# Teensy_Intan_Module_JE_T36_v01_20180628.net
KiCad netlist of a schematic drawn in EAGLE
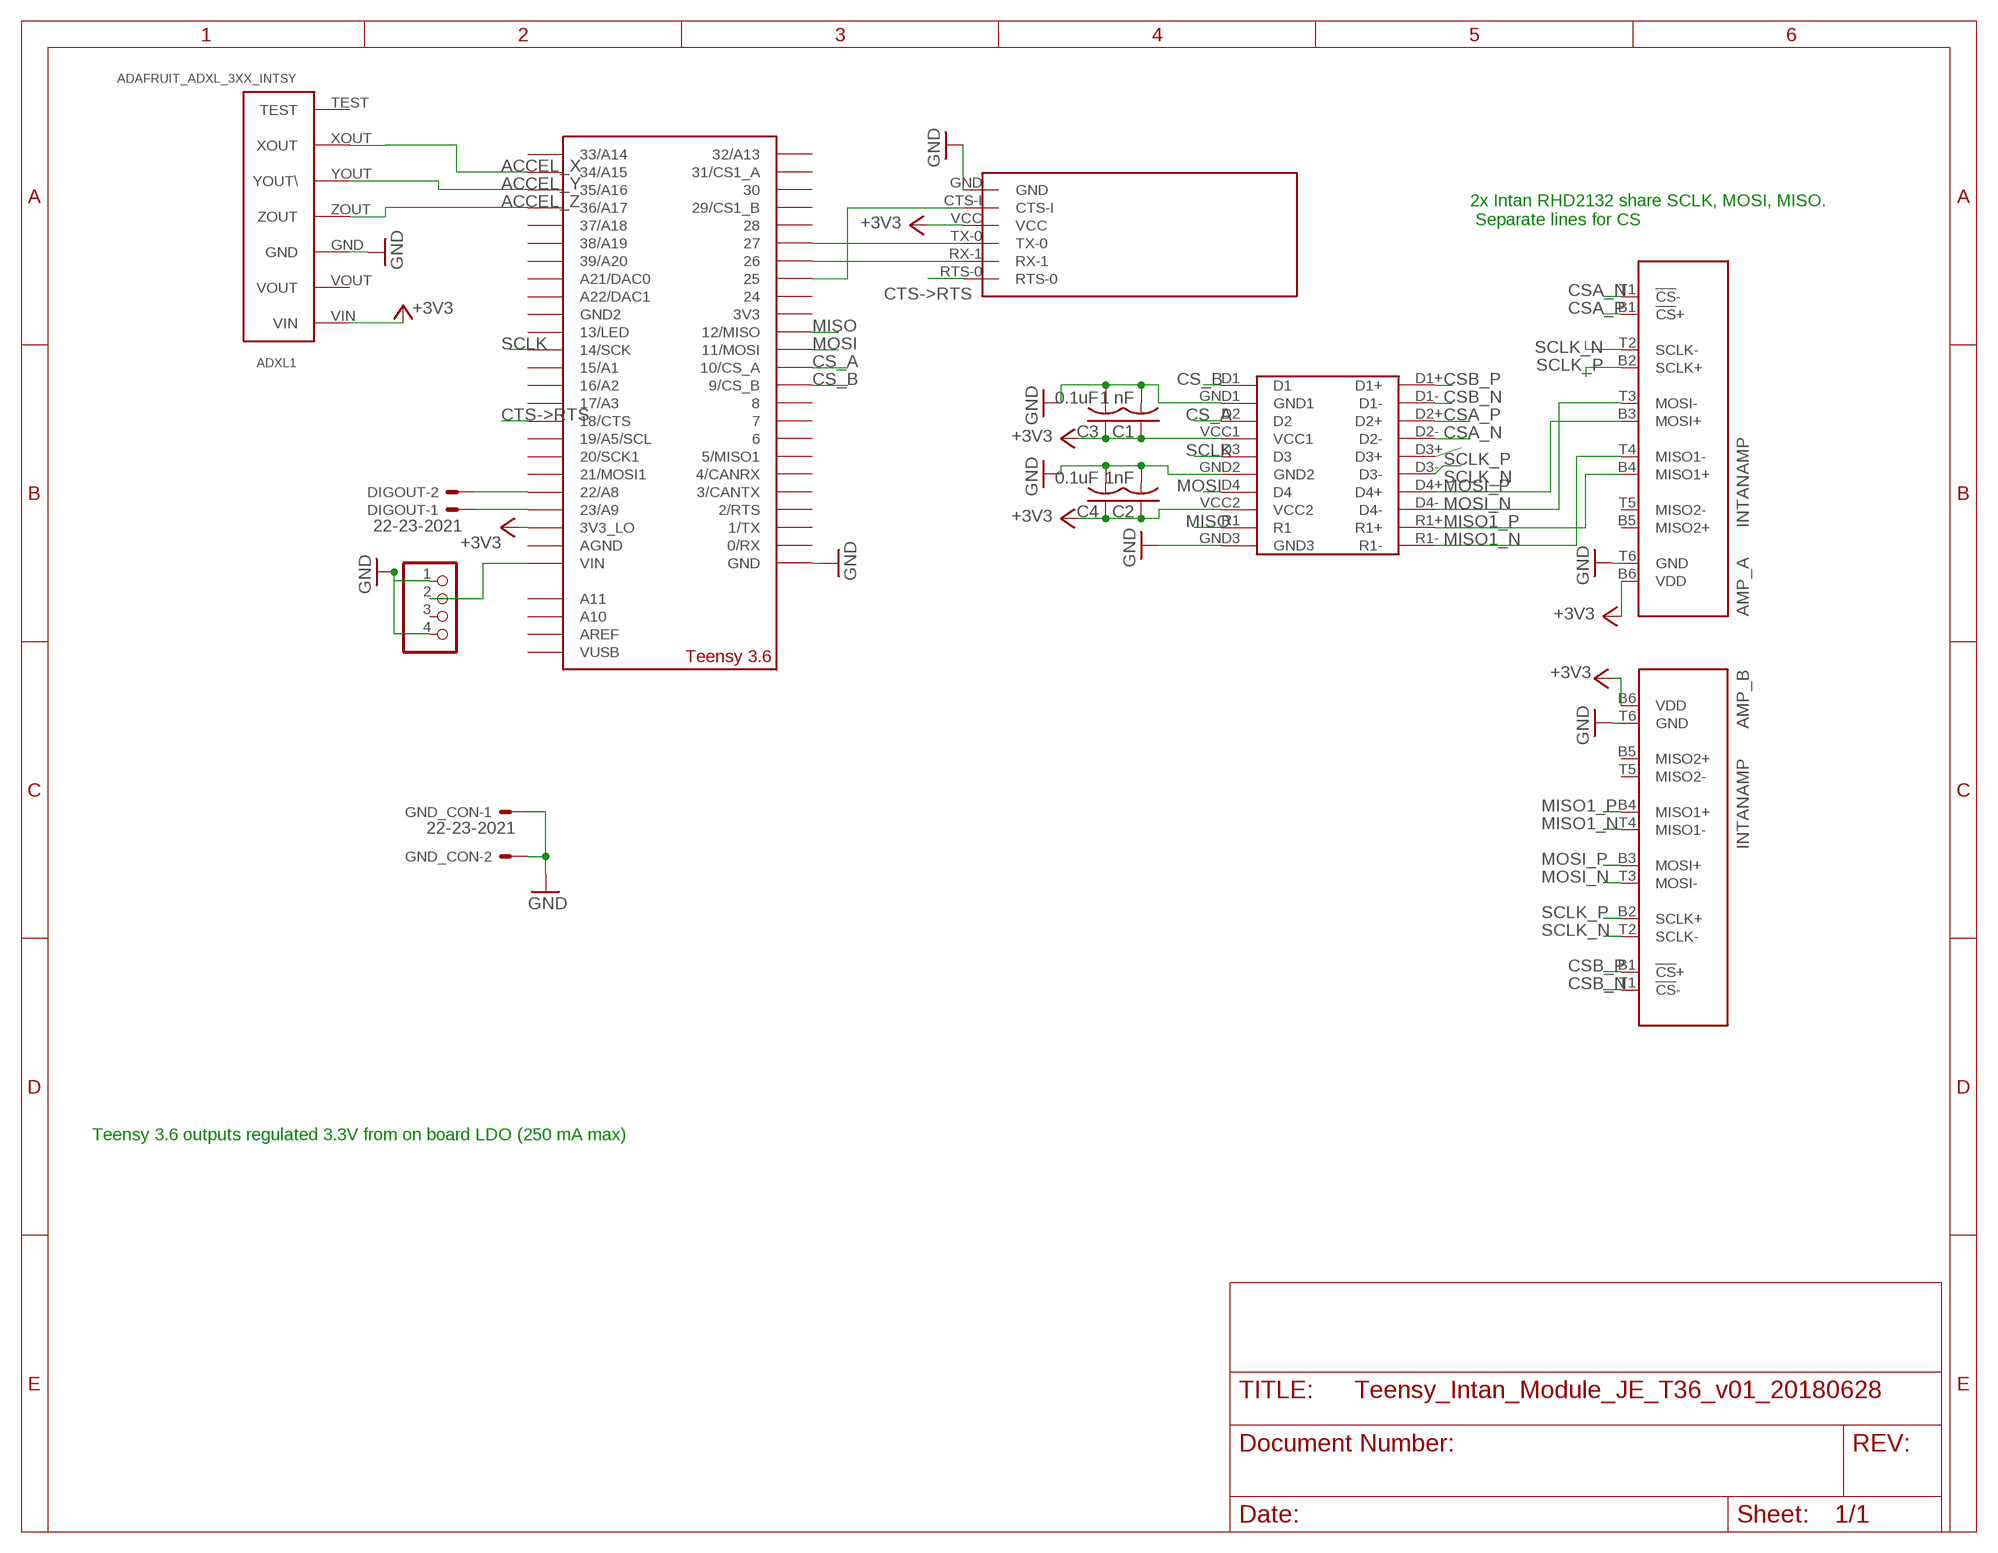
[diagram p0: schematic, sheet 1]

(export (version "E")
  (design (tool "Eeschema 10.0.6"))
  (components
    (comp (ref "ADXL1")
      (value "ADAFRUIT_ADXL_3XX_INTSY")
      (footprint "eagle-import:ADAFRUIT_ADXL_3XX")
      (libsource (lib "eagle-import") (part "ADAFRUIT_ADXL_3XX_INTSY"))
    )
    (comp (ref "AMP_A")
      (value "INTANAMP")
      (footprint "eagle-import:AMPBOARD")
      (libsource (lib "eagle-import") (part "INTANAMP"))
    )
    (comp (ref "AMP_B")
      (value "INTANAMP")
      (footprint "eagle-import:AMPBOARD")
      (libsource (lib "eagle-import") (part "INTANAMP"))
    )
    (comp (ref "C1")
      (value "1 nF")
      (footprint "eagle-import:C025-024X044")
      (libsource (lib "eagle-import") (part "C-US025-024X044"))
    )
    (comp (ref "C2")
      (value "1nF")
      (footprint "eagle-import:C025-024X044")
      (libsource (lib "eagle-import") (part "C-US025-024X044"))
    )
    (comp (ref "C3")
      (value "0.1uF")
      (footprint "eagle-import:C025-024X044")
      (libsource (lib "eagle-import") (part "C-US025-024X044"))
    )
    (comp (ref "C4")
      (value "0.1uF")
      (footprint "eagle-import:C025-024X044")
      (libsource (lib "eagle-import") (part "C-US025-024X044"))
    )
    (comp (ref "DIGOUT")
      (value "22-23-2021")
      (footprint "eagle-import:22-23-2021")
      (fields (field (name "MF") "MOLEX"))
      (libsource (lib "eagle-import") (part "22-23-2021"))
    )
    (comp (ref "GND_CON")
      (value "22-23-2021")
      (footprint "eagle-import:22-23-2021")
      (fields (field (name "MF") "MOLEX"))
      (libsource (lib "eagle-import") (part "22-23-2021"))
    )
    (comp (ref "RN42")
      (value "RN42")
      (footprint "eagle-import:RN42")
      (libsource (lib "eagle-import") (part "RN42"))
    )
    (comp (ref "SW1")
      (value "LiPoIn")
      (footprint "eagle-import:PADS-4")
      (libsource (lib "eagle-import") (part "PADS-4"))
    )
    (comp (ref "U$1")
      (value "SCHMARTBOARD20PIN")
      (footprint "eagle-import:SCHMARTBOARD20PIN")
      (libsource (lib "eagle-import") (part "SCHMARTBOARD20PIN"))
    )
    (comp (ref "U$2")
      (value "TEENSY_3.5/3.6_BASIC")
      (footprint "eagle-import:TEENSY_3.5_3.6_BASIC")
      (libsource (lib "eagle-import") (part "TEENSY_3.5/3.6_BASIC"))
    )
  )
  (nets
    (net (code "1") (name "+3V3") (class "Default")
      (node (ref "ADXL1") (pin "VIN") (pinfunction "VIN_VIN") (pintype "power_in"))
      (node (ref "AMP_A") (pin "B6") (pinfunction "VDD_B6") (pintype "bidirectional"))
      (node (ref "AMP_B") (pin "B6") (pinfunction "VDD_B6") (pintype "bidirectional"))
      (node (ref "C1") (pin "1") (pinfunction "1_1") (pintype "passive"))
      (node (ref "C2") (pin "1") (pinfunction "1_1") (pintype "passive"))
      (node (ref "C3") (pin "1") (pinfunction "1_1") (pintype "passive"))
      (node (ref "C4") (pin "1") (pinfunction "1_1") (pintype "passive"))
      (node (ref "RN42") (pin "VCC") (pinfunction "VCC_VCC") (pintype "bidirectional"))
      (node (ref "U$1") (pin "VCC1") (pinfunction "VCC1_VCC1") (pintype "bidirectional"))
      (node (ref "U$1") (pin "VCC2") (pinfunction "VCC2_VCC2") (pintype "bidirectional"))
      (node (ref "U$2") (pin "3V3_LO") (pinfunction "3V3_LO_3V3_LO") (pintype "bidirectional"))
    )
    (net (code "2") (name "/ACCEL_X") (class "Default")
      (node (ref "ADXL1") (pin "XOUT") (pinfunction "XOUT_XOUT") (pintype "bidirectional"))
      (node (ref "U$2") (pin "34/A15") (pinfunction "34/A15_34/A15") (pintype "input"))
    )
    (net (code "3") (name "/ACCEL_Y") (class "Default")
      (node (ref "ADXL1") (pin "YOUT") (pinfunction "YOUT\\_YOUT") (pintype "bidirectional"))
      (node (ref "U$2") (pin "35/A16") (pinfunction "35/A16_35/A16") (pintype "bidirectional"))
    )
    (net (code "4") (name "/ACCEL_Z") (class "Default")
      (node (ref "ADXL1") (pin "ZOUT") (pinfunction "ZOUT_ZOUT") (pintype "bidirectional"))
      (node (ref "U$2") (pin "36/A17") (pinfunction "36/A17_36/A17") (pintype "bidirectional"))
    )
    (net (code "5") (name "/CSA_N") (class "Default")
      (node (ref "AMP_A") (pin "T1") (pinfunction "~{CS}-_T1") (pintype "bidirectional"))
      (node (ref "U$1") (pin "D2-") (pinfunction "D2-_D2-") (pintype "bidirectional"))
    )
    (net (code "6") (name "/CSA_P") (class "Default")
      (node (ref "AMP_A") (pin "B1") (pinfunction "~{CS}+_B1") (pintype "bidirectional"))
      (node (ref "U$1") (pin "D2+") (pinfunction "D2+_D2+") (pintype "bidirectional"))
    )
    (net (code "7") (name "/CSB_N") (class "Default")
      (node (ref "AMP_B") (pin "T1") (pinfunction "~{CS}-_T1") (pintype "bidirectional"))
      (node (ref "U$1") (pin "D1-") (pinfunction "D1-_D1-") (pintype "bidirectional"))
    )
    (net (code "8") (name "/CSB_P") (class "Default")
      (node (ref "AMP_B") (pin "B1") (pinfunction "~{CS}+_B1") (pintype "bidirectional"))
      (node (ref "U$1") (pin "D1+") (pinfunction "D1+_D1+") (pintype "bidirectional"))
    )
    (net (code "9") (name "/CS_A") (class "Default")
      (node (ref "U$1") (pin "D2") (pinfunction "D2_D2") (pintype "bidirectional"))
      (node (ref "U$2") (pin "10/CS") (pinfunction "10/CS_A_10/CS") (pintype "bidirectional"))
    )
    (net (code "10") (name "/CS_B") (class "Default")
      (node (ref "U$1") (pin "D1") (pinfunction "D1_D1") (pintype "bidirectional"))
      (node (ref "U$2") (pin "9/CS") (pinfunction "9/CS_B_9/CS") (pintype "bidirectional"))
    )
    (net (code "11") (name "/CTS->RTS") (class "Default")
      (node (ref "RN42") (pin "RTS-0") (pinfunction "RTS-0_RTS-0") (pintype "bidirectional"))
      (node (ref "U$2") (pin "18/A4/SDA") (pinfunction "18/CTS_18/A4/SDA") (pintype "bidirectional"))
    )
    (net (code "12") (name "/MISO") (class "Default")
      (node (ref "U$1") (pin "R1") (pinfunction "R1_R1") (pintype "bidirectional"))
      (node (ref "U$2") (pin "12/MISO") (pinfunction "12/MISO_12/MISO") (pintype "bidirectional"))
    )
    (net (code "13") (name "/MISO1_N") (class "Default")
      (node (ref "AMP_A") (pin "T4") (pinfunction "MISO1-_T4") (pintype "bidirectional"))
      (node (ref "AMP_B") (pin "T4") (pinfunction "MISO1-_T4") (pintype "bidirectional"))
      (node (ref "U$1") (pin "R1-") (pinfunction "R1-_R1-") (pintype "bidirectional"))
    )
    (net (code "14") (name "/MISO1_P") (class "Default")
      (node (ref "AMP_A") (pin "B4") (pinfunction "MISO1+_B4") (pintype "bidirectional"))
      (node (ref "AMP_B") (pin "B4") (pinfunction "MISO1+_B4") (pintype "bidirectional"))
      (node (ref "U$1") (pin "R1+") (pinfunction "R1+_R1+") (pintype "bidirectional"))
    )
    (net (code "15") (name "/MOSI") (class "Default")
      (node (ref "U$1") (pin "D4") (pinfunction "D4_D4") (pintype "bidirectional"))
      (node (ref "U$2") (pin "11/MOSI") (pinfunction "11/MOSI_11/MOSI") (pintype "bidirectional"))
    )
    (net (code "16") (name "/MOSI_N") (class "Default")
      (node (ref "AMP_A") (pin "T3") (pinfunction "MOSI-_T3") (pintype "bidirectional"))
      (node (ref "AMP_B") (pin "T3") (pinfunction "MOSI-_T3") (pintype "bidirectional"))
      (node (ref "U$1") (pin "D4-") (pinfunction "D4-_D4-") (pintype "bidirectional"))
    )
    (net (code "17") (name "/MOSI_P") (class "Default")
      (node (ref "AMP_A") (pin "B3") (pinfunction "MOSI+_B3") (pintype "bidirectional"))
      (node (ref "AMP_B") (pin "B3") (pinfunction "MOSI+_B3") (pintype "bidirectional"))
      (node (ref "U$1") (pin "D4+") (pinfunction "D4+_D4+") (pintype "bidirectional"))
    )
    (net (code "18") (name "/SCLK") (class "Default")
      (node (ref "U$1") (pin "D3") (pinfunction "D3_D3") (pintype "bidirectional"))
      (node (ref "U$2") (pin "14/A0") (pinfunction "14/SCK_14/A0") (pintype "bidirectional"))
    )
    (net (code "19") (name "/SCLK_N") (class "Default")
      (node (ref "AMP_A") (pin "T2") (pinfunction "SCLK-_T2") (pintype "bidirectional"))
      (node (ref "AMP_B") (pin "T2") (pinfunction "SCLK-_T2") (pintype "bidirectional"))
      (node (ref "U$1") (pin "D3-") (pinfunction "D3-_D3-") (pintype "bidirectional"))
    )
    (net (code "20") (name "/SCLK_P") (class "Default")
      (node (ref "AMP_A") (pin "B2") (pinfunction "SCLK+_B2") (pintype "bidirectional"))
      (node (ref "AMP_B") (pin "B2") (pinfunction "SCLK+_B2") (pintype "bidirectional"))
      (node (ref "U$1") (pin "D3+") (pinfunction "D3+_D3+") (pintype "bidirectional"))
    )
    (net (code "21") (name "GND") (class "Default")
      (node (ref "ADXL1") (pin "GND") (pinfunction "GND_GND") (pintype "power_in"))
      (node (ref "AMP_A") (pin "T6") (pinfunction "GND_T6") (pintype "power_in"))
      (node (ref "AMP_B") (pin "T6") (pinfunction "GND_T6") (pintype "power_in"))
      (node (ref "C1") (pin "2") (pinfunction "2_2") (pintype "passive"))
      (node (ref "C2") (pin "2") (pinfunction "2_2") (pintype "passive"))
      (node (ref "C3") (pin "2") (pinfunction "2_2") (pintype "passive"))
      (node (ref "C4") (pin "2") (pinfunction "2_2") (pintype "passive"))
      (node (ref "GND_CON") (pin "1") (pinfunction "S_1") (pintype "passive"))
      (node (ref "GND_CON") (pin "2") (pinfunction "S_2") (pintype "passive"))
      (node (ref "RN42") (pin "GND") (pinfunction "GND_GND") (pintype "bidirectional"))
      (node (ref "SW1") (pin "1") (pinfunction "1_1") (pintype "passive"))
      (node (ref "SW1") (pin "4") (pinfunction "4_4") (pintype "passive"))
      (node (ref "U$1") (pin "GND1") (pinfunction "GND1_GND1") (pintype "bidirectional"))
      (node (ref "U$1") (pin "GND2") (pinfunction "GND2_GND2") (pintype "bidirectional"))
      (node (ref "U$1") (pin "GND3") (pinfunction "GND3_GND3") (pintype "bidirectional"))
      (node (ref "U$2") (pin "GND") (pinfunction "GND_GND") (pintype "bidirectional"))
    )
    (net (code "22") (name "Net-(DIGOUTA-S)") (class "Default")
      (node (ref "DIGOUT") (pin "1") (pinfunction "S_1") (pintype "passive"))
      (node (ref "U$2") (pin "23/A9") (pinfunction "23/A9_23/A9") (pintype "bidirectional"))
    )
    (net (code "23") (name "Net-(DIGOUTB-S)") (class "Default")
      (node (ref "DIGOUT") (pin "2") (pinfunction "S_2") (pintype "passive"))
      (node (ref "U$2") (pin "22/A8") (pinfunction "22/A8_22/A8") (pintype "bidirectional"))
    )
    (net (code "24") (name "Net-(RN42-PadCTS-I)") (class "Default")
      (node (ref "RN42") (pin "CTS-I") (pinfunction "CTS-I_CTS-I") (pintype "bidirectional"))
      (node (ref "U$2") (pin "25") (pinfunction "25_25") (pintype "bidirectional"))
    )
    (net (code "25") (name "Net-(RN42-PadRX-1)") (class "Default")
      (node (ref "RN42") (pin "RX-1") (pinfunction "RX-1_RX-1") (pintype "bidirectional"))
      (node (ref "U$2") (pin "26") (pinfunction "26_26") (pintype "bidirectional"))
    )
    (net (code "26") (name "Net-(RN42-PadTX-0)") (class "Default")
      (node (ref "RN42") (pin "TX-0") (pinfunction "TX-0_TX-0") (pintype "bidirectional"))
      (node (ref "U$2") (pin "27") (pinfunction "27_27") (pintype "bidirectional"))
    )
    (net (code "27") (name "Net-(SW1-Pad2)") (class "Default")
      (node (ref "SW1") (pin "2") (pinfunction "2_2") (pintype "passive"))
      (node (ref "U$2") (pin "VIN") (pinfunction "VIN_VIN") (pintype "bidirectional"))
    )
    (net (code "28") (name "unconnected-(ADXL1-PadTEST)") (class "Default")
      (node (ref "ADXL1") (pin "TEST") (pinfunction "TEST_TEST") (pintype "no_connect"))
    )
    (net (code "29") (name "unconnected-(ADXL1-PadVOUT)") (class "Default")
      (node (ref "ADXL1") (pin "VOUT") (pinfunction "VOUT_VOUT") (pintype "bidirectional"))
    )
    (net (code "30") (name "unconnected-(AMP_A-MISO2+-PadB5)") (class "Default")
      (node (ref "AMP_A") (pin "B5") (pinfunction "MISO2+_B5") (pintype "bidirectional"))
    )
    (net (code "31") (name "unconnected-(AMP_A-MISO2--PadT5)") (class "Default")
      (node (ref "AMP_A") (pin "T5") (pinfunction "MISO2-_T5") (pintype "bidirectional"))
    )
    (net (code "32") (name "unconnected-(AMP_B-MISO2+-PadB5)") (class "Default")
      (node (ref "AMP_B") (pin "B5") (pinfunction "MISO2+_B5") (pintype "bidirectional"))
    )
    (net (code "33") (name "unconnected-(AMP_B-MISO2--PadT5)") (class "Default")
      (node (ref "AMP_B") (pin "T5") (pinfunction "MISO2-_T5") (pintype "bidirectional"))
    )
    (net (code "34") (name "unconnected-(SW1-Pad3)") (class "Default")
      (node (ref "SW1") (pin "3") (pinfunction "3_3") (pintype "passive"))
    )
    (net (code "35") (name "unconnected-(U$2-2{slash}RTS-Pad2)") (class "Default")
      (node (ref "U$2") (pin "2") (pinfunction "2/RTS_2") (pintype "bidirectional"))
    )
    (net (code "36") (name "unconnected-(U$2-5{slash}MISO1-Pad5)") (class "Default")
      (node (ref "U$2") (pin "5") (pinfunction "5/MISO1_5") (pintype "bidirectional"))
    )
    (net (code "37") (name "unconnected-(U$2-13{slash}LED-Pad13{slash}SCK)") (class "Default")
      (node (ref "U$2") (pin "13/SCK") (pinfunction "13/LED_13/SCK") (pintype "bidirectional"))
    )
    (net (code "38") (name "unconnected-(U$2-20{slash}SCK1-Pad20{slash}A6)") (class "Default")
      (node (ref "U$2") (pin "20/A6") (pinfunction "20/SCK1_20/A6") (pintype "bidirectional"))
    )
    (net (code "39") (name "unconnected-(U$2-21{slash}MOSI1-Pad21{slash}A7)") (class "Default")
      (node (ref "U$2") (pin "21/A7") (pinfunction "21/MOSI1_21/A7") (pintype "bidirectional"))
    )
    (net (code "40") (name "unconnected-(U$2-29{slash}CS1_B-Pad29)") (class "Default")
      (node (ref "U$2") (pin "29") (pinfunction "29/CS1_B_29") (pintype "bidirectional"))
    )
    (net (code "41") (name "unconnected-(U$2-31{slash}CS1_A-Pad31{slash}A12)") (class "Default")
      (node (ref "U$2") (pin "31/A12") (pinfunction "31/CS1_A_31/A12") (pintype "bidirectional"))
    )
    (net (code "42") (name "unconnected-(U$2-A21{slash}DAC0-Pad21{slash}DAC0)") (class "Default")
      (node (ref "U$2") (pin "21/DAC0") (pinfunction "A21/DAC0_21/DAC0") (pintype "bidirectional"))
    )
    (net (code "43") (name "unconnected-(U$2-Pad0{slash}RX)") (class "Default")
      (node (ref "U$2") (pin "0/RX") (pinfunction "0/RX_0/RX") (pintype "bidirectional"))
    )
    (net (code "44") (name "unconnected-(U$2-Pad1{slash}TX)") (class "Default")
      (node (ref "U$2") (pin "1/TX") (pinfunction "1/TX_1/TX") (pintype "bidirectional"))
    )
    (net (code "45") (name "unconnected-(U$2-Pad3V3)") (class "Default")
      (node (ref "U$2") (pin "3V3") (pinfunction "3V3_3V3") (pintype "bidirectional"))
    )
    (net (code "46") (name "unconnected-(U$2-Pad3{slash}CANTX)") (class "Default")
      (node (ref "U$2") (pin "3/CANTX") (pinfunction "3/CANTX_3/CANTX") (pintype "bidirectional"))
    )
    (net (code "47") (name "unconnected-(U$2-Pad4{slash}CANRX)") (class "Default")
      (node (ref "U$2") (pin "4/CANRX") (pinfunction "4/CANRX_4/CANRX") (pintype "bidirectional"))
    )
    (net (code "48") (name "unconnected-(U$2-Pad6)") (class "Default")
      (node (ref "U$2") (pin "6") (pinfunction "6_6") (pintype "bidirectional"))
    )
    (net (code "49") (name "unconnected-(U$2-Pad7)") (class "Default")
      (node (ref "U$2") (pin "7") (pinfunction "7_7") (pintype "bidirectional"))
    )
    (net (code "50") (name "unconnected-(U$2-Pad8)") (class "Default")
      (node (ref "U$2") (pin "8") (pinfunction "8_8") (pintype "bidirectional"))
    )
    (net (code "51") (name "unconnected-(U$2-Pad15{slash}A1)") (class "Default")
      (node (ref "U$2") (pin "15/A1") (pinfunction "15/A1_15/A1") (pintype "bidirectional"))
    )
    (net (code "52") (name "unconnected-(U$2-Pad16{slash}A2)") (class "Default")
      (node (ref "U$2") (pin "16/A2") (pinfunction "16/A2_16/A2") (pintype "bidirectional"))
    )
    (net (code "53") (name "unconnected-(U$2-Pad17{slash}A3)") (class "Default")
      (node (ref "U$2") (pin "17/A3") (pinfunction "17/A3_17/A3") (pintype "bidirectional"))
    )
    (net (code "54") (name "unconnected-(U$2-Pad19{slash}A5{slash}SCL)") (class "Default")
      (node (ref "U$2") (pin "19/A5/SCL") (pinfunction "19/A5/SCL_19/A5/SCL") (pintype "bidirectional"))
    )
    (net (code "55") (name "unconnected-(U$2-Pad24)") (class "Default")
      (node (ref "U$2") (pin "24") (pinfunction "24_24") (pintype "bidirectional"))
    )
    (net (code "56") (name "unconnected-(U$2-Pad28)") (class "Default")
      (node (ref "U$2") (pin "28") (pinfunction "28_28") (pintype "bidirectional"))
    )
    (net (code "57") (name "unconnected-(U$2-Pad30)") (class "Default")
      (node (ref "U$2") (pin "30") (pinfunction "30_30") (pintype "bidirectional"))
    )
    (net (code "58") (name "unconnected-(U$2-Pad32{slash}A13)") (class "Default")
      (node (ref "U$2") (pin "32/A13") (pinfunction "32/A13_32/A13") (pintype "bidirectional"))
    )
    (net (code "59") (name "unconnected-(U$2-Pad33{slash}A14)") (class "Default")
      (node (ref "U$2") (pin "33/A14") (pinfunction "33/A14_33/A14") (pintype "bidirectional"))
    )
    (net (code "60") (name "unconnected-(U$2-Pad37{slash}A18)") (class "Default")
      (node (ref "U$2") (pin "37/A18") (pinfunction "37/A18_37/A18") (pintype "bidirectional"))
    )
    (net (code "61") (name "unconnected-(U$2-Pad38{slash}A19)") (class "Default")
      (node (ref "U$2") (pin "38/A19") (pinfunction "38/A19_38/A19") (pintype "bidirectional"))
    )
    (net (code "62") (name "unconnected-(U$2-Pad39{slash}A20)") (class "Default")
      (node (ref "U$2") (pin "39/A20") (pinfunction "39/A20_39/A20") (pintype "bidirectional"))
    )
    (net (code "63") (name "unconnected-(U$2-PadA10)") (class "Default")
      (node (ref "U$2") (pin "A10") (pinfunction "A10_A10") (pintype "bidirectional"))
    )
    (net (code "64") (name "unconnected-(U$2-PadA11)") (class "Default")
      (node (ref "U$2") (pin "A11") (pinfunction "A11_A11") (pintype "bidirectional"))
    )
    (net (code "65") (name "unconnected-(U$2-PadA22{slash}DAC1)") (class "Default")
      (node (ref "U$2") (pin "A22/DAC1") (pinfunction "A22/DAC1_A22/DAC1") (pintype "bidirectional"))
    )
    (net (code "66") (name "unconnected-(U$2-PadAGND)") (class "Default")
      (node (ref "U$2") (pin "AGND") (pinfunction "AGND_AGND") (pintype "bidirectional"))
    )
    (net (code "67") (name "unconnected-(U$2-PadAREF)") (class "Default")
      (node (ref "U$2") (pin "AREF") (pinfunction "AREF_AREF") (pintype "bidirectional"))
    )
    (net (code "68") (name "unconnected-(U$2-PadGND2)") (class "Default")
      (node (ref "U$2") (pin "GND2") (pinfunction "GND2_GND2") (pintype "bidirectional"))
    )
    (net (code "69") (name "unconnected-(U$2-PadVUSB)") (class "Default")
      (node (ref "U$2") (pin "VUSB") (pinfunction "VUSB_VUSB") (pintype "bidirectional"))
    )
  )
)
